# ControlBoard.net
KiCad netlist of a schematic drawn in Altium Designer
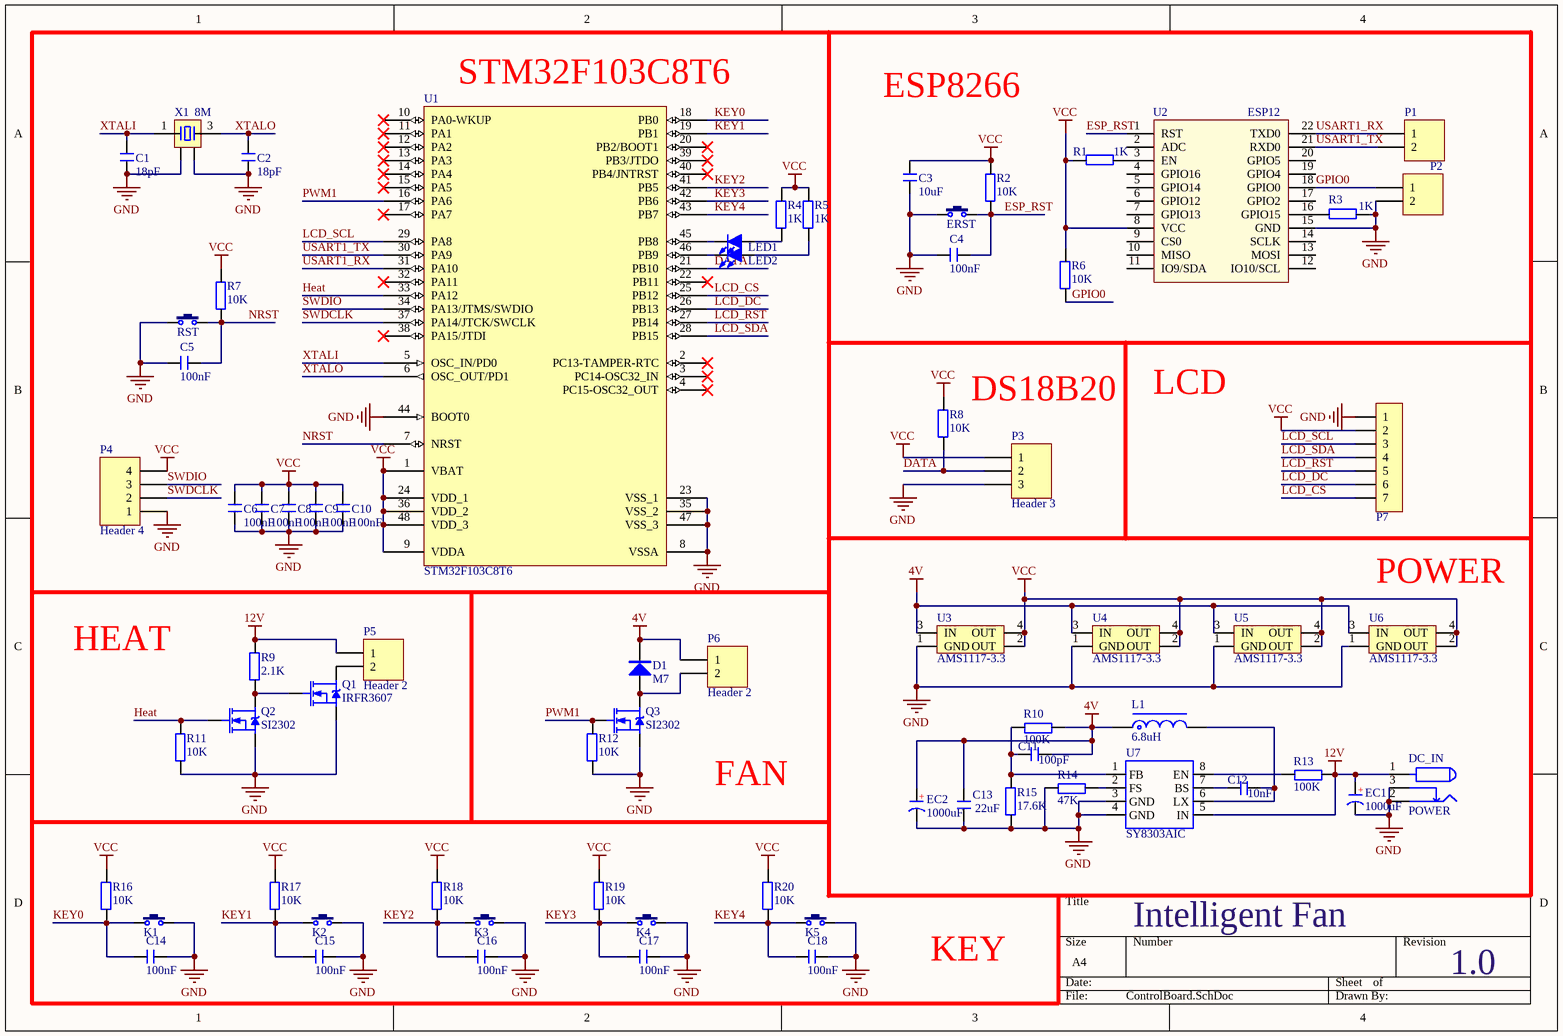
[diagram p0: ControlBoard.SchDoc]

(export (version "E")
  (design (tool "Eeschema 10.0.6"))
  (components
    (comp (ref "C1")
      (value "18pF")
      (footprint "C 0603")
      (description "无极性贴片电容")
      (fields (field (name "Comment") "C"))
      (libsource (lib "电阻-电容-电感") (part "C"))
    )
    (comp (ref "C2")
      (value "18pF")
      (footprint "C 0603")
      (description "无极性贴片电容")
      (fields (field (name "Comment") "C"))
      (libsource (lib "电阻-电容-电感") (part "C"))
    )
    (comp (ref "C3")
      (value "10uF")
      (footprint "C 1206")
      (description "无极性贴片电容")
      (fields (field (name "Comment") "C"))
      (libsource (lib "电阻-电容-电感") (part "C"))
    )
    (comp (ref "C4")
      (value "100nF")
      (footprint "C 0603")
      (description "无极性贴片电容")
      (fields (field (name "Comment") "C"))
      (libsource (lib "电阻-电容-电感") (part "C"))
    )
    (comp (ref "C5")
      (value "100nF")
      (footprint "C 0603")
      (description "无极性贴片电容")
      (fields (field (name "Comment") "C"))
      (libsource (lib "电阻-电容-电感") (part "C"))
    )
    (comp (ref "C6")
      (value "100nF")
      (footprint "C 0603")
      (description "无极性贴片电容")
      (fields (field (name "Comment") "C"))
      (libsource (lib "电阻-电容-电感") (part "C"))
    )
    (comp (ref "C7")
      (value "100nF")
      (footprint "C 0603")
      (description "无极性贴片电容")
      (fields (field (name "Comment") "C"))
      (libsource (lib "电阻-电容-电感") (part "C"))
    )
    (comp (ref "C8")
      (value "100nF")
      (footprint "C 0603")
      (description "无极性贴片电容")
      (fields (field (name "Comment") "C"))
      (libsource (lib "电阻-电容-电感") (part "C"))
    )
    (comp (ref "C9")
      (value "100nF")
      (footprint "C 0603")
      (description "无极性贴片电容")
      (fields (field (name "Comment") "C"))
      (libsource (lib "电阻-电容-电感") (part "C"))
    )
    (comp (ref "C10")
      (value "100nF")
      (footprint "C 0603")
      (description "无极性贴片电容")
      (fields (field (name "Comment") "C"))
      (libsource (lib "电阻-电容-电感") (part "C"))
    )
    (comp (ref "C11")
      (value "100pF")
      (footprint "C 0603")
      (description "无极性贴片电容")
      (fields (field (name "Comment") "C"))
      (libsource (lib "电阻-电容-电感") (part "C"))
    )
    (comp (ref "C12")
      (value "10nF")
      (footprint "C 0603")
      (description "无极性贴片电容")
      (fields (field (name "Comment") "C"))
      (libsource (lib "电阻-电容-电感") (part "C"))
    )
    (comp (ref "C13")
      (value "22uF")
      (footprint "C 0603")
      (description "无极性贴片电容")
      (fields (field (name "Comment") "C"))
      (libsource (lib "电阻-电容-电感") (part "C"))
    )
    (comp (ref "C14")
      (value "100nF")
      (footprint "C 0603")
      (description "无极性贴片电容")
      (fields (field (name "Comment") "C"))
      (libsource (lib "电阻-电容-电感") (part "C"))
    )
    (comp (ref "C15")
      (value "100nF")
      (footprint "C 0603")
      (description "无极性贴片电容")
      (fields (field (name "Comment") "C"))
      (libsource (lib "电阻-电容-电感") (part "C"))
    )
    (comp (ref "C16")
      (value "100nF")
      (footprint "C 0603")
      (description "无极性贴片电容")
      (fields (field (name "Comment") "C"))
      (libsource (lib "电阻-电容-电感") (part "C"))
    )
    (comp (ref "C17")
      (value "100nF")
      (footprint "C 0603")
      (description "无极性贴片电容")
      (fields (field (name "Comment") "C"))
      (libsource (lib "电阻-电容-电感") (part "C"))
    )
    (comp (ref "C18")
      (value "100nF")
      (footprint "C 0603")
      (description "无极性贴片电容")
      (fields (field (name "Comment") "C"))
      (libsource (lib "电阻-电容-电感") (part "C"))
    )
    (comp (ref "D1")
      (value "M7")
      (footprint "SMA")
      (description "整流二极管")
      (fields (field (name "版权归属") "源创客"))
      (libsource (lib "二极管") (part "M7"))
    )
    (comp (ref "DC_IN")
      (value "POWER")
      (footprint "DC10B")
      (libsource (lib "阿波罗STM32F4&F7&H7底板封装库") (part "POW"))
    )
    (comp (ref "EC1")
      (value "1000uF")
      (footprint "CM F(10*10.2)")
      (description "贴片电解电容")
      (fields (field (name "Comment") "C-CM"))
      (libsource (lib "电阻-电容-电感") (part "C-CM"))
    )
    (comp (ref "EC2")
      (value "1000uF")
      (footprint "CM F(10*10.2)")
      (description "贴片电解电容")
      (fields (field (name "Comment") "C-CM"))
      (libsource (lib "电阻-电容-电感") (part "C-CM"))
    )
    (comp (ref "ERST")
      (value "3x6x5")
      (footprint "TSW SMD-3*6*4.3")
      (description "3x6轻触开关")
      (fields (field (name "版权归属") "源创客"))
      (libsource (lib "按键-开关") (part "TSW 3x6"))
    )
    (comp (ref "K1")
      (value "3x6x5")
      (footprint "TSW SMD-3*6*4.3")
      (description "3x6轻触开关")
      (fields (field (name "版权归属") "源创客"))
      (libsource (lib "按键-开关") (part "TSW 3x6"))
    )
    (comp (ref "K2")
      (value "3x6x5")
      (footprint "TSW SMD-3*6*4.3")
      (description "3x6轻触开关")
      (fields (field (name "版权归属") "源创客"))
      (libsource (lib "按键-开关") (part "TSW 3x6"))
    )
    (comp (ref "K3")
      (value "3x6x5")
      (footprint "TSW SMD-3*6*4.3")
      (description "3x6轻触开关")
      (fields (field (name "版权归属") "源创客"))
      (libsource (lib "按键-开关") (part "TSW 3x6"))
    )
    (comp (ref "K4")
      (value "3x6x5")
      (footprint "TSW SMD-3*6*4.3")
      (description "3x6轻触开关")
      (fields (field (name "版权归属") "源创客"))
      (libsource (lib "按键-开关") (part "TSW 3x6"))
    )
    (comp (ref "K5")
      (value "3x6x5")
      (footprint "TSW SMD-3*6*4.3")
      (description "3x6轻触开关")
      (fields (field (name "版权归属") "源创客"))
      (libsource (lib "按键-开关") (part "TSW 3x6"))
    )
    (comp (ref "L1")
      (value "6.8uH")
      (footprint "CDRH74")
      (description "功率屏蔽电感")
      (fields (field (name "Comment") "2A"))
      (libsource (lib "电阻-电容-电感") (part "L-CDRH"))
    )
    (comp (ref "LED1")
      (value "红色")
      (footprint "LED 0603B")
      (description "贴片LED")
      (fields (field (name "版权归属") "源创客"))
      (libsource (lib "LED") (part "LED-SMD"))
    )
    (comp (ref "LED2")
      (value "红色")
      (footprint "LED 0603B")
      (description "贴片LED")
      (fields (field (name "版权归属") "源创客"))
      (libsource (lib "LED") (part "LED-SMD"))
    )
    (comp (ref "P1")
      (value "Header 2")
      (footprint "HDR1X2")
      (description "Header, 2-Pin")
      (fields (field (name "PUBLISHER") "Altium Limited"))
      (libsource (lib "Miscellaneous Connectors") (part "Header 2"))
    )
    (comp (ref "P2")
      (value "Header 2")
      (footprint "HDR1X2")
      (description "Header, 2-Pin")
      (fields (field (name "PUBLISHER") "Altium Limited"))
      (libsource (lib "Miscellaneous Connectors") (part "Header 2"))
    )
    (comp (ref "P3")
      (value "Header 3")
      (footprint "HDR1X3")
      (description "Header, 3-Pin")
      (fields (field (name "PUBLISHER") "Altium Limited"))
      (libsource (lib "Miscellaneous Connectors") (part "Header 3"))
    )
    (comp (ref "P4")
      (value "Header 4")
      (footprint "HDR1X4")
      (description "Header, 4-Pin")
      (fields (field (name "PUBLISHER") "Altium Limited"))
      (libsource (lib "Miscellaneous Connectors") (part "Header 4"))
    )
    (comp (ref "P5")
      (value "Header 2")
      (footprint "HDR1X2")
      (description "Header, 2-Pin")
      (fields (field (name "PUBLISHER") "Altium Limited"))
      (libsource (lib "Miscellaneous Connectors") (part "Header 2"))
    )
    (comp (ref "P6")
      (value "Header 2")
      (footprint "HDR1X2")
      (description "Header, 2-Pin")
      (fields (field (name "PUBLISHER") "Altium Limited"))
      (libsource (lib "Miscellaneous Connectors") (part "Header 2"))
    )
    (comp (ref "P7")
      (value "HDR-1X7")
      (footprint "HDR1X7")
      (description "7P接插件")
      (fields (field (name "版权归属") "源创客"))
      (libsource (lib "接插件") (part "Header 7"))
    )
    (comp (ref "Q1")
      (value "IRFR3607")
      (footprint "TO252")
      (description "Nmos")
      (libsource (lib "晶体管") (part "IRFR3607"))
    )
    (comp (ref "Q2")
      (value "SI2302")
      (footprint "SOT23-3N")
      (description "N沟道场效应管")
      (libsource (lib "晶体管") (part "SI2302"))
    )
    (comp (ref "Q3")
      (value "SI2302")
      (footprint "SOT23-3N")
      (description "N沟道场效应管")
      (libsource (lib "晶体管") (part "SI2302"))
    )
    (comp (ref "R1") (value "1K") (footprint "R 0603") (libsource (lib "STM32H743核心板封装库") (part "R")))
    (comp (ref "R2") (value "10K") (footprint "R 0603") (libsource (lib "STM32H743核心板封装库") (part "R")))
    (comp (ref "R3") (value "1K") (footprint "R 0603") (libsource (lib "STM32H743核心板封装库") (part "R")))
    (comp (ref "R4") (value "1K") (footprint "R 0603") (libsource (lib "STM32H743核心板封装库") (part "R")))
    (comp (ref "R5") (value "1K") (footprint "R 0603") (libsource (lib "STM32H743核心板封装库") (part "R")))
    (comp (ref "R6") (value "10K") (footprint "R 0603") (libsource (lib "STM32H743核心板封装库") (part "R")))
    (comp (ref "R7") (value "10K") (footprint "R 0603") (libsource (lib "STM32H743核心板封装库") (part "R")))
    (comp (ref "R8") (value "10K") (footprint "R 0603") (libsource (lib "STM32H743核心板封装库") (part "R")))
    (comp (ref "R9") (value "2.1K") (footprint "R 0603") (libsource (lib "STM32H743核心板封装库") (part "R")))
    (comp (ref "R10") (value "100K") (footprint "R 0603") (libsource (lib "STM32H743核心板封装库") (part "R")))
    (comp (ref "R11") (value "10K") (footprint "R 0603") (libsource (lib "STM32H743核心板封装库") (part "R")))
    (comp (ref "R12") (value "10K") (footprint "R 0603") (libsource (lib "STM32H743核心板封装库") (part "R")))
    (comp (ref "R13") (value "100K") (footprint "R 0603") (libsource (lib "STM32H743核心板封装库") (part "R")))
    (comp (ref "R14") (value "47K") (footprint "R 0603") (libsource (lib "STM32H743核心板封装库") (part "R")))
    (comp (ref "R15") (value "17.6K") (footprint "R 0603") (libsource (lib "STM32H743核心板封装库") (part "R")))
    (comp (ref "R16") (value "10K") (footprint "R 0603") (libsource (lib "STM32H743核心板封装库") (part "R")))
    (comp (ref "R17") (value "10K") (footprint "R 0603") (libsource (lib "STM32H743核心板封装库") (part "R")))
    (comp (ref "R18") (value "10K") (footprint "R 0603") (libsource (lib "STM32H743核心板封装库") (part "R")))
    (comp (ref "R19") (value "10K") (footprint "R 0603") (libsource (lib "STM32H743核心板封装库") (part "R")))
    (comp (ref "R20") (value "10K") (footprint "R 0603") (libsource (lib "STM32H743核心板封装库") (part "R")))
    (comp (ref "RST")
      (value "3x6x5")
      (footprint "TSW SMD-3*6*4.3")
      (description "3x6轻触开关")
      (fields (field (name "版权归属") "源创客"))
      (libsource (lib "按键-开关") (part "TSW 3x6"))
    )
    (comp (ref "U1")
      (value "STM32F103C8T6")
      (footprint "LQFP48 7X7_N")
      (description "Flash:64/RAM:20/IO:36")
      (fields (field (name "版权归属") "源创客"))
      (libsource (lib "STM32系列单片机") (part "STM32F103C8"))
    )
    (comp (ref "U2")
      (value "ESP12")
      (footprint "ESP-12E&F Module")
      (description "ESP-12E&F Module")
      (libsource (lib "ESP-12改后") (part "ESP-12E&F Module"))
    )
    (comp (ref "U3")
      (value "AMS1117-3.3")
      (footprint "AMS1117")
      (libsource (lib "阿波罗STM32F4&F7&H7底板封装库") (part "AMS1117"))
    )
    (comp (ref "U4")
      (value "AMS1117-3.3")
      (footprint "AMS1117")
      (libsource (lib "阿波罗STM32F4&F7&H7底板封装库") (part "AMS1117"))
    )
    (comp (ref "U5")
      (value "AMS1117-3.3")
      (footprint "AMS1117")
      (libsource (lib "阿波罗STM32F4&F7&H7底板封装库") (part "AMS1117"))
    )
    (comp (ref "U6")
      (value "AMS1117-3.3")
      (footprint "AMS1117")
      (libsource (lib "阿波罗STM32F4&F7&H7底板封装库") (part "AMS1117"))
    )
    (comp (ref "U7")
      (value "SY8303AIC")
      (footprint "SOT23_8")
      (description "Buck升压芯片")
      (libsource (lib "IC芯片") (part "SY8303AIC"))
    )
    (comp (ref "X1")
      (value "8M")
      (footprint "XTAL-3225")
      (description "4脚晶振")
      (fields (field (name "版权归属") "源创客"))
      (libsource (lib "保险丝-晶振") (part "XTAL-4"))
    )
  )
  (nets
    (net (code "1") (name "/DATA") (class "Default")
      (node (ref "P3") (pin "2") (pinfunction "2_2") (pintype "passive"))
      (node (ref "R8") (pin "2") (pintype "passive"))
      (node (ref "U1") (pin "21") (pinfunction "PB10_21") (pintype "bidirectional"))
    )
    (net (code "2") (name "/ESP_RST") (class "Default")
      (node (ref "C4") (pin "2") (pinfunction "2_2") (pintype "passive"))
      (node (ref "ERST") (pin "2") (pinfunction "2_2") (pintype "passive"))
      (node (ref "R2") (pin "2") (pintype "passive"))
      (node (ref "U2") (pin "1") (pinfunction "RST_1") (pintype "passive"))
    )
    (net (code "3") (name "/GPIO0") (class "Default")
      (node (ref "P2") (pin "1") (pinfunction "1_1") (pintype "passive"))
      (node (ref "R6") (pin "2") (pintype "passive"))
      (node (ref "U2") (pin "18") (pinfunction "GPIO0_18") (pintype "passive"))
    )
    (net (code "4") (name "/Heat") (class "Default")
      (node (ref "Q2") (pin "1") (pinfunction "G_1") (pintype "passive"))
      (node (ref "R11") (pin "1") (pintype "passive"))
      (node (ref "U1") (pin "33") (pinfunction "PA12_33") (pintype "bidirectional"))
    )
    (net (code "5") (name "/KEY0") (class "Default")
      (node (ref "C14") (pin "1") (pinfunction "1_1") (pintype "passive"))
      (node (ref "K1") (pin "1") (pinfunction "1_1") (pintype "passive"))
      (node (ref "R16") (pin "2") (pintype "passive"))
      (node (ref "U1") (pin "18") (pinfunction "PB0_18") (pintype "bidirectional"))
    )
    (net (code "6") (name "/KEY1") (class "Default")
      (node (ref "C15") (pin "1") (pinfunction "1_1") (pintype "passive"))
      (node (ref "K2") (pin "1") (pinfunction "1_1") (pintype "passive"))
      (node (ref "R17") (pin "2") (pintype "passive"))
      (node (ref "U1") (pin "19") (pinfunction "PB1_19") (pintype "bidirectional"))
    )
    (net (code "7") (name "/KEY2") (class "Default")
      (node (ref "C16") (pin "1") (pinfunction "1_1") (pintype "passive"))
      (node (ref "K3") (pin "1") (pinfunction "1_1") (pintype "passive"))
      (node (ref "R18") (pin "2") (pintype "passive"))
      (node (ref "U1") (pin "41") (pinfunction "PB5_41") (pintype "bidirectional"))
    )
    (net (code "8") (name "/KEY3") (class "Default")
      (node (ref "C17") (pin "1") (pinfunction "1_1") (pintype "passive"))
      (node (ref "K4") (pin "1") (pinfunction "1_1") (pintype "passive"))
      (node (ref "R19") (pin "2") (pintype "passive"))
      (node (ref "U1") (pin "42") (pinfunction "PB6_42") (pintype "bidirectional"))
    )
    (net (code "9") (name "/KEY4") (class "Default")
      (node (ref "C18") (pin "1") (pinfunction "1_1") (pintype "passive"))
      (node (ref "K5") (pin "1") (pinfunction "1_1") (pintype "passive"))
      (node (ref "R20") (pin "2") (pintype "passive"))
      (node (ref "U1") (pin "43") (pinfunction "PB7_43") (pintype "bidirectional"))
    )
    (net (code "10") (name "/LCD_CS") (class "Default")
      (node (ref "P7") (pin "7") (pinfunction "7_7") (pintype "passive"))
      (node (ref "U1") (pin "25") (pinfunction "PB12_25") (pintype "bidirectional"))
    )
    (net (code "11") (name "/LCD_DC") (class "Default")
      (node (ref "P7") (pin "6") (pinfunction "6_6") (pintype "passive"))
      (node (ref "U1") (pin "26") (pinfunction "PB13_26") (pintype "bidirectional"))
    )
    (net (code "12") (name "/LCD_RST") (class "Default")
      (node (ref "P7") (pin "5") (pinfunction "5_5") (pintype "passive"))
      (node (ref "U1") (pin "27") (pinfunction "PB14_27") (pintype "bidirectional"))
    )
    (net (code "13") (name "/LCD_SCL") (class "Default")
      (node (ref "P7") (pin "3") (pinfunction "3_3") (pintype "passive"))
      (node (ref "U1") (pin "29") (pinfunction "PA8_29") (pintype "bidirectional"))
    )
    (net (code "14") (name "/LCD_SDA") (class "Default")
      (node (ref "P7") (pin "4") (pinfunction "4_4") (pintype "passive"))
      (node (ref "U1") (pin "28") (pinfunction "PB15_28") (pintype "bidirectional"))
    )
    (net (code "15") (name "/NRST") (class "Default")
      (node (ref "C5") (pin "2") (pinfunction "2_2") (pintype "passive"))
      (node (ref "R7") (pin "2") (pintype "passive"))
      (node (ref "RST") (pin "2") (pinfunction "2_2") (pintype "passive"))
      (node (ref "U1") (pin "7") (pinfunction "NRST_7") (pintype "bidirectional"))
    )
    (net (code "16") (name "/PWM1") (class "Default")
      (node (ref "Q3") (pin "1") (pinfunction "G_1") (pintype "passive"))
      (node (ref "R12") (pin "1") (pintype "passive"))
      (node (ref "U1") (pin "16") (pinfunction "PA6_16") (pintype "bidirectional"))
    )
    (net (code "17") (name "/SWDCLK") (class "Default")
      (node (ref "P4") (pin "2") (pinfunction "2_2") (pintype "passive"))
      (node (ref "U1") (pin "37") (pinfunction "PA14/JTCK/SWCLK_37") (pintype "bidirectional"))
    )
    (net (code "18") (name "/SWDIO") (class "Default")
      (node (ref "P4") (pin "3") (pinfunction "3_3") (pintype "passive"))
      (node (ref "U1") (pin "34") (pinfunction "PA13/JTMS/SWDIO_34") (pintype "bidirectional"))
    )
    (net (code "19") (name "/USART1_RX") (class "Default")
      (node (ref "P1") (pin "1") (pinfunction "1_1") (pintype "passive"))
      (node (ref "U1") (pin "31") (pinfunction "PA10_31") (pintype "bidirectional"))
      (node (ref "U2") (pin "22") (pinfunction "TXD0_22") (pintype "passive"))
    )
    (net (code "20") (name "/USART1_TX") (class "Default")
      (node (ref "P1") (pin "2") (pinfunction "2_2") (pintype "passive"))
      (node (ref "U1") (pin "30") (pinfunction "PA9_30") (pintype "bidirectional"))
      (node (ref "U2") (pin "21") (pinfunction "RXD0_21") (pintype "passive"))
    )
    (net (code "21") (name "/XTALI") (class "Default")
      (node (ref "C1") (pin "2") (pinfunction "2_2") (pintype "passive"))
      (node (ref "U1") (pin "5") (pinfunction "OSC_IN/PD0_5") (pintype "input"))
      (node (ref "X1") (pin "1") (pinfunction "1_1") (pintype "passive"))
    )
    (net (code "22") (name "/XTALO") (class "Default")
      (node (ref "C2") (pin "2") (pinfunction "2_2") (pintype "passive"))
      (node (ref "U1") (pin "6") (pinfunction "OSC_OUT/PD1_6") (pintype "output"))
      (node (ref "X1") (pin "3") (pinfunction "3_3") (pintype "passive"))
    )
    (net (code "23") (name "4V") (class "Default")
      (node (ref "C11") (pin "2") (pinfunction "2_2") (pintype "passive"))
      (node (ref "C13") (pin "1") (pinfunction "1_1") (pintype "passive"))
      (node (ref "D1") (pin "2") (pinfunction "K_2") (pintype "passive"))
      (node (ref "EC2") (pin "1") (pinfunction "A_1") (pintype "passive"))
      (node (ref "L1") (pin "1") (pinfunction "1_1") (pintype "passive"))
      (node (ref "P6") (pin "1") (pinfunction "1_1") (pintype "passive"))
      (node (ref "R10") (pin "2") (pintype "passive"))
      (node (ref "U3") (pin "3") (pinfunction "IN_3") (pintype "passive"))
      (node (ref "U4") (pin "3") (pinfunction "IN_3") (pintype "passive"))
      (node (ref "U5") (pin "3") (pinfunction "IN_3") (pintype "passive"))
      (node (ref "U6") (pin "3") (pinfunction "IN_3") (pintype "passive"))
    )
    (net (code "24") (name "12V") (class "Default")
      (node (ref "DC_IN") (pin "1") (pintype "passive"))
      (node (ref "EC1") (pin "1") (pinfunction "A_1") (pintype "passive"))
      (node (ref "P5") (pin "1") (pinfunction "1_1") (pintype "passive"))
      (node (ref "R13") (pin "2") (pintype "passive"))
      (node (ref "R9") (pin "1") (pintype "passive"))
      (node (ref "U7") (pin "5") (pinfunction "IN_5") (pintype "power_in"))
    )
    (net (code "25") (name "GND") (class "Default")
      (node (ref "C1") (pin "1") (pinfunction "1_1") (pintype "passive"))
      (node (ref "C10") (pin "1") (pinfunction "1_1") (pintype "passive"))
      (node (ref "C13") (pin "2") (pinfunction "2_2") (pintype "passive"))
      (node (ref "C14") (pin "2") (pinfunction "2_2") (pintype "passive"))
      (node (ref "C15") (pin "2") (pinfunction "2_2") (pintype "passive"))
      (node (ref "C16") (pin "2") (pinfunction "2_2") (pintype "passive"))
      (node (ref "C17") (pin "2") (pinfunction "2_2") (pintype "passive"))
      (node (ref "C18") (pin "2") (pinfunction "2_2") (pintype "passive"))
      (node (ref "C2") (pin "1") (pinfunction "1_1") (pintype "passive"))
      (node (ref "C3") (pin "1") (pinfunction "1_1") (pintype "passive"))
      (node (ref "C4") (pin "1") (pinfunction "1_1") (pintype "passive"))
      (node (ref "C5") (pin "1") (pinfunction "1_1") (pintype "passive"))
      (node (ref "C6") (pin "1") (pinfunction "1_1") (pintype "passive"))
      (node (ref "C7") (pin "1") (pinfunction "1_1") (pintype "passive"))
      (node (ref "C8") (pin "1") (pinfunction "1_1") (pintype "passive"))
      (node (ref "C9") (pin "1") (pinfunction "1_1") (pintype "passive"))
      (node (ref "DC_IN") (pin "2") (pintype "passive"))
      (node (ref "DC_IN") (pin "3") (pintype "passive"))
      (node (ref "EC1") (pin "2") (pinfunction "K_2") (pintype "passive"))
      (node (ref "EC2") (pin "2") (pinfunction "K_2") (pintype "passive"))
      (node (ref "ERST") (pin "1") (pinfunction "1_1") (pintype "passive"))
      (node (ref "K1") (pin "2") (pinfunction "2_2") (pintype "passive"))
      (node (ref "K2") (pin "2") (pinfunction "2_2") (pintype "passive"))
      (node (ref "K3") (pin "2") (pinfunction "2_2") (pintype "passive"))
      (node (ref "K4") (pin "2") (pinfunction "2_2") (pintype "passive"))
      (node (ref "K5") (pin "2") (pinfunction "2_2") (pintype "passive"))
      (node (ref "P2") (pin "2") (pinfunction "2_2") (pintype "passive"))
      (node (ref "P3") (pin "3") (pinfunction "3_3") (pintype "passive"))
      (node (ref "P4") (pin "1") (pinfunction "1_1") (pintype "passive"))
      (node (ref "P7") (pin "1") (pinfunction "1_1") (pintype "passive"))
      (node (ref "Q1") (pin "3") (pinfunction "S_3") (pintype "passive"))
      (node (ref "Q2") (pin "2") (pinfunction "S_2") (pintype "passive"))
      (node (ref "Q3") (pin "2") (pinfunction "S_2") (pintype "passive"))
      (node (ref "R11") (pin "2") (pintype "passive"))
      (node (ref "R12") (pin "2") (pintype "passive"))
      (node (ref "R14") (pin "1") (pintype "passive"))
      (node (ref "R15") (pin "2") (pintype "passive"))
      (node (ref "R3") (pin "1") (pintype "passive"))
      (node (ref "RST") (pin "1") (pinfunction "1_1") (pintype "passive"))
      (node (ref "U1") (pin "23") (pinfunction "VSS_1_23") (pintype "power_in"))
      (node (ref "U1") (pin "35") (pinfunction "VSS_2_35") (pintype "power_in"))
      (node (ref "U1") (pin "44") (pinfunction "BOOT0_44") (pintype "input"))
      (node (ref "U1") (pin "47") (pinfunction "VSS_3_47") (pintype "power_in"))
      (node (ref "U1") (pin "8") (pinfunction "VSSA_8") (pintype "power_in"))
      (node (ref "U2") (pin "15") (pinfunction "GND_15") (pintype "passive"))
      (node (ref "U3") (pin "1") (pinfunction "GND_1") (pintype "passive"))
      (node (ref "U4") (pin "1") (pinfunction "GND_1") (pintype "passive"))
      (node (ref "U5") (pin "1") (pinfunction "GND_1") (pintype "passive"))
      (node (ref "U6") (pin "1") (pinfunction "GND_1") (pintype "passive"))
      (node (ref "U7") (pin "3") (pinfunction "GND_3") (pintype "power_in"))
      (node (ref "U7") (pin "4") (pinfunction "GND_4") (pintype "power_in"))
      (node (ref "X1") (pin "2") (pinfunction "2_2") (pintype "passive"))
      (node (ref "X1") (pin "4") (pinfunction "4_4") (pintype "passive"))
    )
    (net (code "26") (name "Net-(D1-A)") (class "Default")
      (node (ref "D1") (pin "1") (pinfunction "A_1") (pintype "passive"))
      (node (ref "P6") (pin "2") (pinfunction "2_2") (pintype "passive"))
      (node (ref "Q3") (pin "3") (pinfunction "D_3") (pintype "passive"))
    )
    (net (code "27") (name "Net-(LED1-A)") (class "Default")
      (node (ref "LED1") (pin "1") (pinfunction "A_1") (pintype "passive"))
      (node (ref "R4") (pin "2") (pintype "passive"))
    )
    (net (code "28") (name "Net-(LED1-K)") (class "Default")
      (node (ref "LED1") (pin "2") (pinfunction "K_2") (pintype "passive"))
      (node (ref "U1") (pin "45") (pinfunction "PB8_45") (pintype "bidirectional"))
    )
    (net (code "29") (name "Net-(LED2-A)") (class "Default")
      (node (ref "LED2") (pin "1") (pinfunction "A_1") (pintype "passive"))
      (node (ref "R5") (pin "2") (pintype "passive"))
    )
    (net (code "30") (name "Net-(LED2-K)") (class "Default")
      (node (ref "LED2") (pin "2") (pinfunction "K_2") (pintype "passive"))
      (node (ref "U1") (pin "46") (pinfunction "PB9_46") (pintype "bidirectional"))
    )
    (net (code "31") (name "Net-(Q1-D)") (class "Default")
      (node (ref "P5") (pin "2") (pinfunction "2_2") (pintype "passive"))
      (node (ref "Q1") (pin "2") (pinfunction "D_2") (pintype "passive"))
    )
    (net (code "32") (name "Net-(Q1-G)") (class "Default")
      (node (ref "Q1") (pin "1") (pinfunction "G_1") (pintype "passive"))
      (node (ref "Q2") (pin "3") (pinfunction "D_3") (pintype "passive"))
      (node (ref "R9") (pin "2") (pintype "passive"))
    )
    (net (code "33") (name "Net-(U2-EN)") (class "Default")
      (node (ref "R1") (pin "1") (pintype "passive"))
      (node (ref "U2") (pin "3") (pinfunction "EN_3") (pintype "passive"))
    )
    (net (code "34") (name "Net-(U2-GPIO15)") (class "Default")
      (node (ref "R3") (pin "2") (pintype "passive"))
      (node (ref "U2") (pin "16") (pinfunction "GPIO15_16") (pintype "passive"))
    )
    (net (code "35") (name "Net-(U7-BS)") (class "Default")
      (node (ref "C12") (pin "1") (pinfunction "1_1") (pintype "passive"))
      (node (ref "U7") (pin "7") (pinfunction "BS_7") (pintype "power_in"))
    )
    (net (code "36") (name "Net-(U7-EN)") (class "Default")
      (node (ref "R13") (pin "1") (pintype "passive"))
      (node (ref "U7") (pin "8") (pinfunction "EN_8") (pintype "power_in"))
    )
    (net (code "37") (name "Net-(U7-FB)") (class "Default")
      (node (ref "C11") (pin "1") (pinfunction "1_1") (pintype "passive"))
      (node (ref "R10") (pin "1") (pintype "passive"))
      (node (ref "R15") (pin "1") (pintype "passive"))
      (node (ref "U7") (pin "1") (pinfunction "FB_1") (pintype "power_in"))
    )
    (net (code "38") (name "Net-(U7-FS)") (class "Default")
      (node (ref "R14") (pin "2") (pintype "passive"))
      (node (ref "U7") (pin "2") (pinfunction "FS_2") (pintype "power_in"))
    )
    (net (code "39") (name "Net-(U7-LX)") (class "Default")
      (node (ref "C12") (pin "2") (pinfunction "2_2") (pintype "passive"))
      (node (ref "L1") (pin "2") (pinfunction "2_2") (pintype "passive"))
      (node (ref "U7") (pin "6") (pinfunction "LX_6") (pintype "power_in"))
    )
    (net (code "40") (name "VCC") (class "Default")
      (node (ref "C10") (pin "2") (pinfunction "2_2") (pintype "passive"))
      (node (ref "C3") (pin "2") (pinfunction "2_2") (pintype "passive"))
      (node (ref "C6") (pin "2") (pinfunction "2_2") (pintype "passive"))
      (node (ref "C7") (pin "2") (pinfunction "2_2") (pintype "passive"))
      (node (ref "C8") (pin "2") (pinfunction "2_2") (pintype "passive"))
      (node (ref "C9") (pin "2") (pinfunction "2_2") (pintype "passive"))
      (node (ref "P3") (pin "1") (pinfunction "1_1") (pintype "passive"))
      (node (ref "P4") (pin "4") (pinfunction "4_4") (pintype "passive"))
      (node (ref "P7") (pin "2") (pinfunction "2_2") (pintype "passive"))
      (node (ref "R1") (pin "2") (pintype "passive"))
      (node (ref "R16") (pin "1") (pintype "passive"))
      (node (ref "R17") (pin "1") (pintype "passive"))
      (node (ref "R18") (pin "1") (pintype "passive"))
      (node (ref "R19") (pin "1") (pintype "passive"))
      (node (ref "R2") (pin "1") (pintype "passive"))
      (node (ref "R20") (pin "1") (pintype "passive"))
      (node (ref "R4") (pin "1") (pintype "passive"))
      (node (ref "R5") (pin "1") (pintype "passive"))
      (node (ref "R6") (pin "1") (pintype "passive"))
      (node (ref "R7") (pin "1") (pintype "passive"))
      (node (ref "R8") (pin "1") (pintype "passive"))
      (node (ref "U1") (pin "1") (pinfunction "VBAT_1") (pintype "power_in"))
      (node (ref "U1") (pin "24") (pinfunction "VDD_1_24") (pintype "power_in"))
      (node (ref "U1") (pin "36") (pinfunction "VDD_2_36") (pintype "power_in"))
      (node (ref "U1") (pin "48") (pinfunction "VDD_3_48") (pintype "power_in"))
      (node (ref "U1") (pin "9") (pinfunction "VDDA_9") (pintype "power_in"))
      (node (ref "U2") (pin "8") (pinfunction "VCC_8") (pintype "passive"))
      (node (ref "U3") (pin "2") (pinfunction "OUT_2") (pintype "passive"))
      (node (ref "U3") (pin "4") (pinfunction "OUT_4") (pintype "passive"))
      (node (ref "U4") (pin "2") (pinfunction "OUT_2") (pintype "passive"))
      (node (ref "U4") (pin "4") (pinfunction "OUT_4") (pintype "passive"))
      (node (ref "U5") (pin "2") (pinfunction "OUT_2") (pintype "passive"))
      (node (ref "U5") (pin "4") (pinfunction "OUT_4") (pintype "passive"))
      (node (ref "U6") (pin "2") (pinfunction "OUT_2") (pintype "passive"))
      (node (ref "U6") (pin "4") (pinfunction "OUT_4") (pintype "passive"))
    )
    (net (code "41") (name "unconnected-(U1-PA0-WKUP-Pad10)") (class "Default")
      (node (ref "U1") (pin "10") (pinfunction "PA0-WKUP_10") (pintype "bidirectional+no_connect"))
    )
    (net (code "42") (name "unconnected-(U1-PA1-Pad11)") (class "Default")
      (node (ref "U1") (pin "11") (pinfunction "PA1_11") (pintype "bidirectional+no_connect"))
    )
    (net (code "43") (name "unconnected-(U1-PA2-Pad12)") (class "Default")
      (node (ref "U1") (pin "12") (pinfunction "PA2_12") (pintype "bidirectional+no_connect"))
    )
    (net (code "44") (name "unconnected-(U1-PA3-Pad13)") (class "Default")
      (node (ref "U1") (pin "13") (pinfunction "PA3_13") (pintype "bidirectional+no_connect"))
    )
    (net (code "45") (name "unconnected-(U1-PA4-Pad14)") (class "Default")
      (node (ref "U1") (pin "14") (pinfunction "PA4_14") (pintype "bidirectional+no_connect"))
    )
    (net (code "46") (name "unconnected-(U1-PA5-Pad15)") (class "Default")
      (node (ref "U1") (pin "15") (pinfunction "PA5_15") (pintype "bidirectional+no_connect"))
    )
    (net (code "47") (name "unconnected-(U1-PA7-Pad17)") (class "Default")
      (node (ref "U1") (pin "17") (pinfunction "PA7_17") (pintype "bidirectional+no_connect"))
    )
    (net (code "48") (name "unconnected-(U1-PA11-Pad32)") (class "Default")
      (node (ref "U1") (pin "32") (pinfunction "PA11_32") (pintype "bidirectional+no_connect"))
    )
    (net (code "49") (name "unconnected-(U1-PA15{slash}JTDI-Pad38)") (class "Default")
      (node (ref "U1") (pin "38") (pinfunction "PA15/JTDI_38") (pintype "bidirectional+no_connect"))
    )
    (net (code "50") (name "unconnected-(U1-PB2{slash}BOOT1-Pad20)") (class "Default")
      (node (ref "U1") (pin "20") (pinfunction "PB2/BOOT1_20") (pintype "bidirectional+no_connect"))
    )
    (net (code "51") (name "unconnected-(U1-PB3{slash}JTDO-Pad39)") (class "Default")
      (node (ref "U1") (pin "39") (pinfunction "PB3/JTDO_39") (pintype "bidirectional+no_connect"))
    )
    (net (code "52") (name "unconnected-(U1-PB4{slash}JNTRST-Pad40)") (class "Default")
      (node (ref "U1") (pin "40") (pinfunction "PB4/JNTRST_40") (pintype "bidirectional+no_connect"))
    )
    (net (code "53") (name "unconnected-(U1-PB11-Pad22)") (class "Default")
      (node (ref "U1") (pin "22") (pinfunction "PB11_22") (pintype "bidirectional+no_connect"))
    )
    (net (code "54") (name "unconnected-(U1-PC13-TAMPER-RTC-Pad2)") (class "Default")
      (node (ref "U1") (pin "2") (pinfunction "PC13-TAMPER-RTC_2") (pintype "bidirectional+no_connect"))
    )
    (net (code "55") (name "unconnected-(U1-PC14-OSC32_IN-Pad3)") (class "Default")
      (node (ref "U1") (pin "3") (pinfunction "PC14-OSC32_IN_3") (pintype "bidirectional+no_connect"))
    )
    (net (code "56") (name "unconnected-(U1-PC15-OSC32_OUT-Pad4)") (class "Default")
      (node (ref "U1") (pin "4") (pinfunction "PC15-OSC32_OUT_4") (pintype "bidirectional+no_connect"))
    )
    (net (code "57") (name "unconnected-(U2-ADC-Pad2)") (class "Default")
      (node (ref "U2") (pin "2") (pinfunction "ADC_2") (pintype "passive"))
    )
    (net (code "58") (name "unconnected-(U2-CS0-Pad9)") (class "Default")
      (node (ref "U2") (pin "9") (pinfunction "CS0_9") (pintype "passive"))
    )
    (net (code "59") (name "unconnected-(U2-GPIO2-Pad17)") (class "Default")
      (node (ref "U2") (pin "17") (pinfunction "GPIO2_17") (pintype "passive"))
    )
    (net (code "60") (name "unconnected-(U2-GPIO4-Pad19)") (class "Default")
      (node (ref "U2") (pin "19") (pinfunction "GPIO4_19") (pintype "passive"))
    )
    (net (code "61") (name "unconnected-(U2-GPIO5-Pad20)") (class "Default")
      (node (ref "U2") (pin "20") (pinfunction "GPIO5_20") (pintype "passive"))
    )
    (net (code "62") (name "unconnected-(U2-GPIO12-Pad6)") (class "Default")
      (node (ref "U2") (pin "6") (pinfunction "GPIO12_6") (pintype "passive"))
    )
    (net (code "63") (name "unconnected-(U2-GPIO13-Pad7)") (class "Default")
      (node (ref "U2") (pin "7") (pinfunction "GPIO13_7") (pintype "passive"))
    )
    (net (code "64") (name "unconnected-(U2-GPIO14-Pad5)") (class "Default")
      (node (ref "U2") (pin "5") (pinfunction "GPIO14_5") (pintype "passive"))
    )
    (net (code "65") (name "unconnected-(U2-GPIO16-Pad4)") (class "Default")
      (node (ref "U2") (pin "4") (pinfunction "GPIO16_4") (pintype "passive"))
    )
    (net (code "66") (name "unconnected-(U2-IO9{slash}SDA-Pad11)") (class "Default")
      (node (ref "U2") (pin "11") (pinfunction "IO9/SDA_11") (pintype "passive"))
    )
    (net (code "67") (name "unconnected-(U2-IO10{slash}SCL-Pad12)") (class "Default")
      (node (ref "U2") (pin "12") (pinfunction "IO10/SCL_12") (pintype "passive"))
    )
    (net (code "68") (name "unconnected-(U2-MISO-Pad10)") (class "Default")
      (node (ref "U2") (pin "10") (pinfunction "MISO_10") (pintype "passive"))
    )
    (net (code "69") (name "unconnected-(U2-MOSI-Pad13)") (class "Default")
      (node (ref "U2") (pin "13") (pinfunction "MOSI_13") (pintype "passive"))
    )
    (net (code "70") (name "unconnected-(U2-SCLK-Pad14)") (class "Default")
      (node (ref "U2") (pin "14") (pinfunction "SCLK_14") (pintype "passive"))
    )
  )
)
